# BATT_BUTTONS.net
KiCad netlist of a schematic drawn in EAGLE
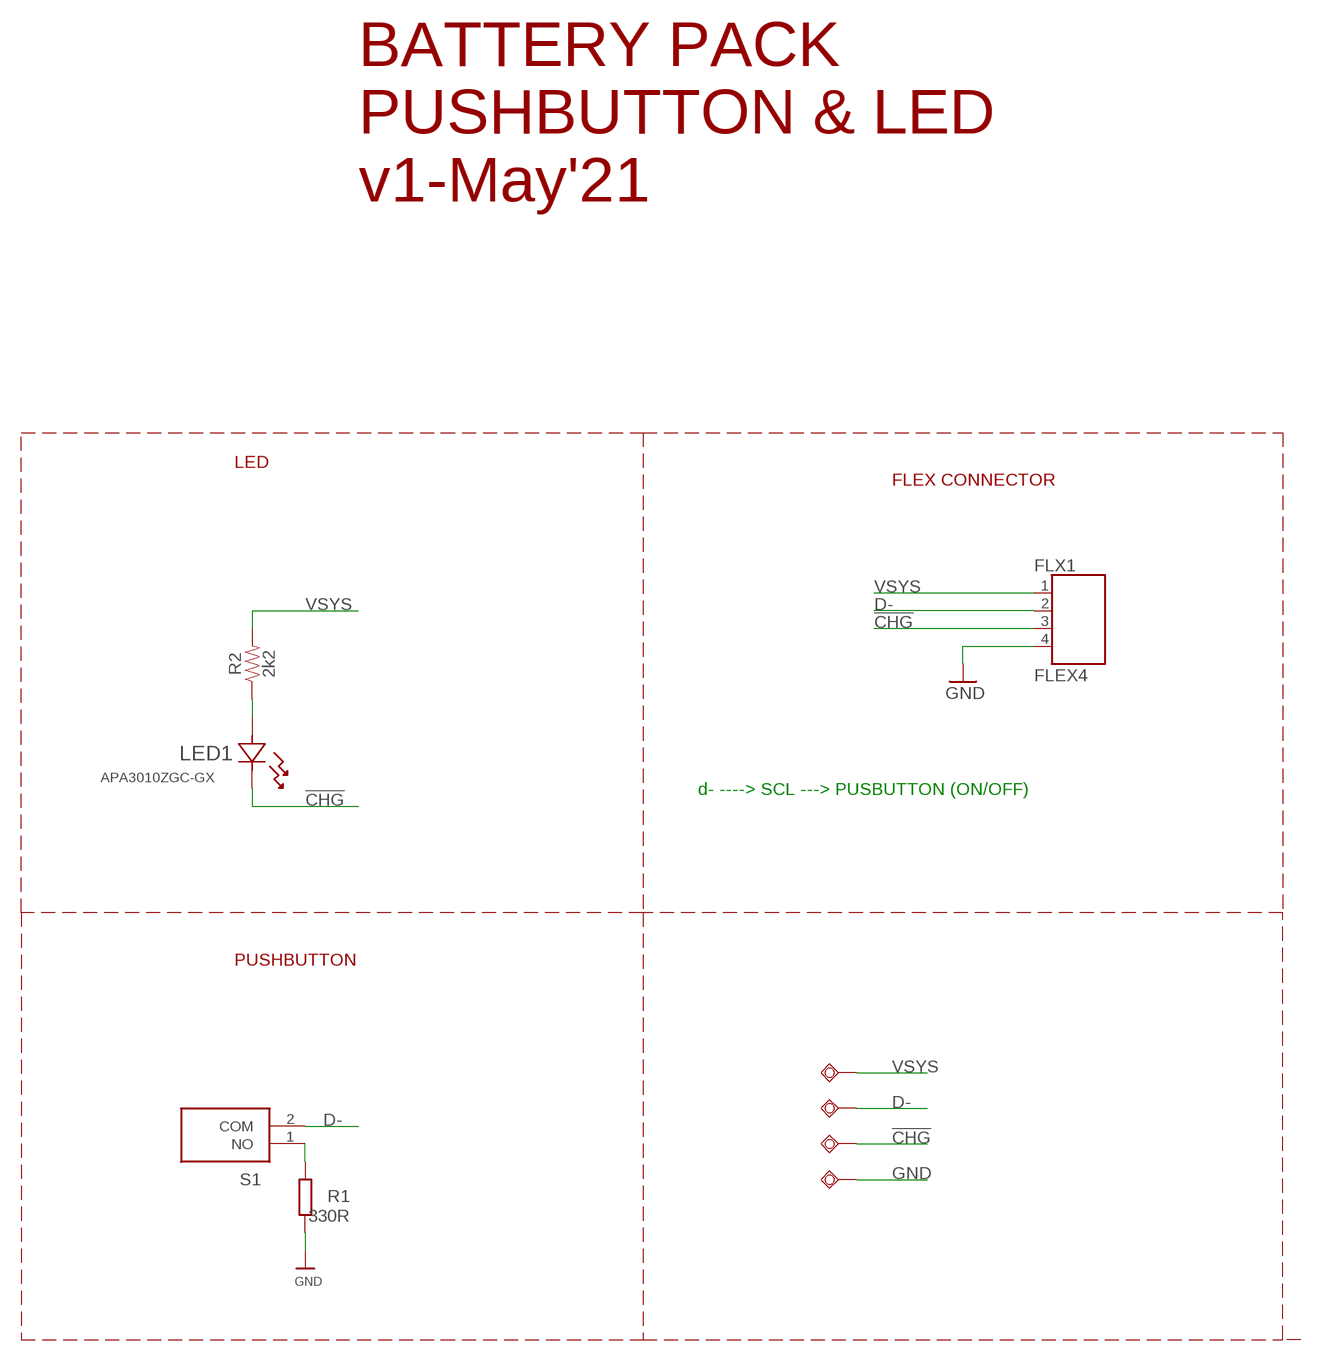
[diagram p0: schematic, sheet 1]

(export (version "E")
  (design (tool "Eeschema 10.0.6"))
  (components
    (comp (ref "!CHG")
      (value "TESTPAD_TPSQB1,27")
      (footprint "eagle-import:TESTPAD_B1,27")
      (libsource (lib "eagle-import") (part "TESTPAD_TPSQB1,27"))
    )
    (comp (ref "D-")
      (value "TESTPAD_TPSQB1,27")
      (footprint "eagle-import:TESTPAD_B1,27")
      (libsource (lib "eagle-import") (part "TESTPAD_TPSQB1,27"))
    )
    (comp (ref "FLX1")
      (value "FLEX4")
      (footprint "eagle-import:FLEX4")
      (libsource (lib "eagle-import") (part "FLEX4"))
    )
    (comp (ref "GND")
      (value "TESTPAD_TPSQB1,27")
      (footprint "eagle-import:TESTPAD_B1,27")
      (libsource (lib "eagle-import") (part "TESTPAD_TPSQB1,27"))
    )
    (comp (ref "LED1")
      (value "APA3010ZGC-GX")
      (footprint "eagle-import:LED_APA3010SRCPRV-GX_KNB")
      (fields
        (field (name "MANUFACTURER_PART_NUMBER") "APA3010SRCPRV-GX")
        (field (name "COPYRIGHT") "Copyright (C) 2018 Accelerated Designs. All rights reserved")
      )
      (libsource (lib "eagle-import") (part "APA3010SRCPRV-GX"))
    )
    (comp (ref "R1")
      (value "330R")
      (footprint "eagle-import:R0603")
      (libsource (lib "eagle-import") (part "R-EU_R0603"))
    )
    (comp (ref "R2")
      (value "2k2")
      (footprint "eagle-import:0402")
      (libsource (lib "eagle-import") (part "RESISTOR0402"))
    )
    (comp (ref "S1")
      (value "KXT311LHS")
      (footprint "eagle-import:KXT311LHS")
      (fields (field (name "MOUSER_PART_NUMBER") "611-KXT311LHS"))
      (libsource (lib "eagle-import") (part "KXT311LHS"))
    )
    (comp (ref "VSYS")
      (value "TESTPAD_TPSQB1,27")
      (footprint "eagle-import:TESTPAD_B1,27")
      (libsource (lib "eagle-import") (part "TESTPAD_TPSQB1,27"))
    )
  )
  (nets
    (net (code "1") (name "/D-") (class "Default")
      (node (ref "D-") (pin "TP") (pinfunction "TP_TP") (pintype "input"))
      (node (ref "FLX1") (pin "2") (pinfunction "2_2") (pintype "passive"))
      (node (ref "S1") (pin "2") (pinfunction "COM_2") (pintype "bidirectional"))
    )
    (net (code "2") (name "/VSYS") (class "Default")
      (node (ref "FLX1") (pin "1") (pinfunction "1_1") (pintype "passive"))
      (node (ref "R2") (pin "2") (pinfunction "2_2") (pintype "passive"))
      (node (ref "VSYS") (pin "TP") (pinfunction "TP_TP") (pintype "input"))
    )
    (net (code "3") (name "/~{CHG}") (class "Default")
      (node (ref "!CHG") (pin "TP") (pinfunction "TP_TP") (pintype "input"))
      (node (ref "FLX1") (pin "3") (pinfunction "3_3") (pintype "passive"))
      (node (ref "LED1") (pin "1") (pinfunction "1_1") (pintype "passive"))
    )
    (net (code "4") (name "GND") (class "Default")
      (node (ref "FLX1") (pin "4") (pinfunction "4_4") (pintype "passive"))
      (node (ref "GND") (pin "TP") (pinfunction "TP_TP") (pintype "input"))
      (node (ref "R1") (pin "1") (pinfunction "1_1") (pintype "passive"))
    )
    (net (code "5") (name "Net-(LED1-Pad2)") (class "Default")
      (node (ref "LED1") (pin "2") (pinfunction "2_2") (pintype "passive"))
      (node (ref "R2") (pin "1") (pinfunction "1_1") (pintype "passive"))
    )
    (net (code "6") (name "Net-(S1-NO)") (class "Default")
      (node (ref "R1") (pin "2") (pinfunction "2_2") (pintype "passive"))
      (node (ref "S1") (pin "1") (pinfunction "NO_1") (pintype "bidirectional"))
    )
  )
)
